# AV_Channel.net
KiCad netlist of a schematic drawn in Altium Designer
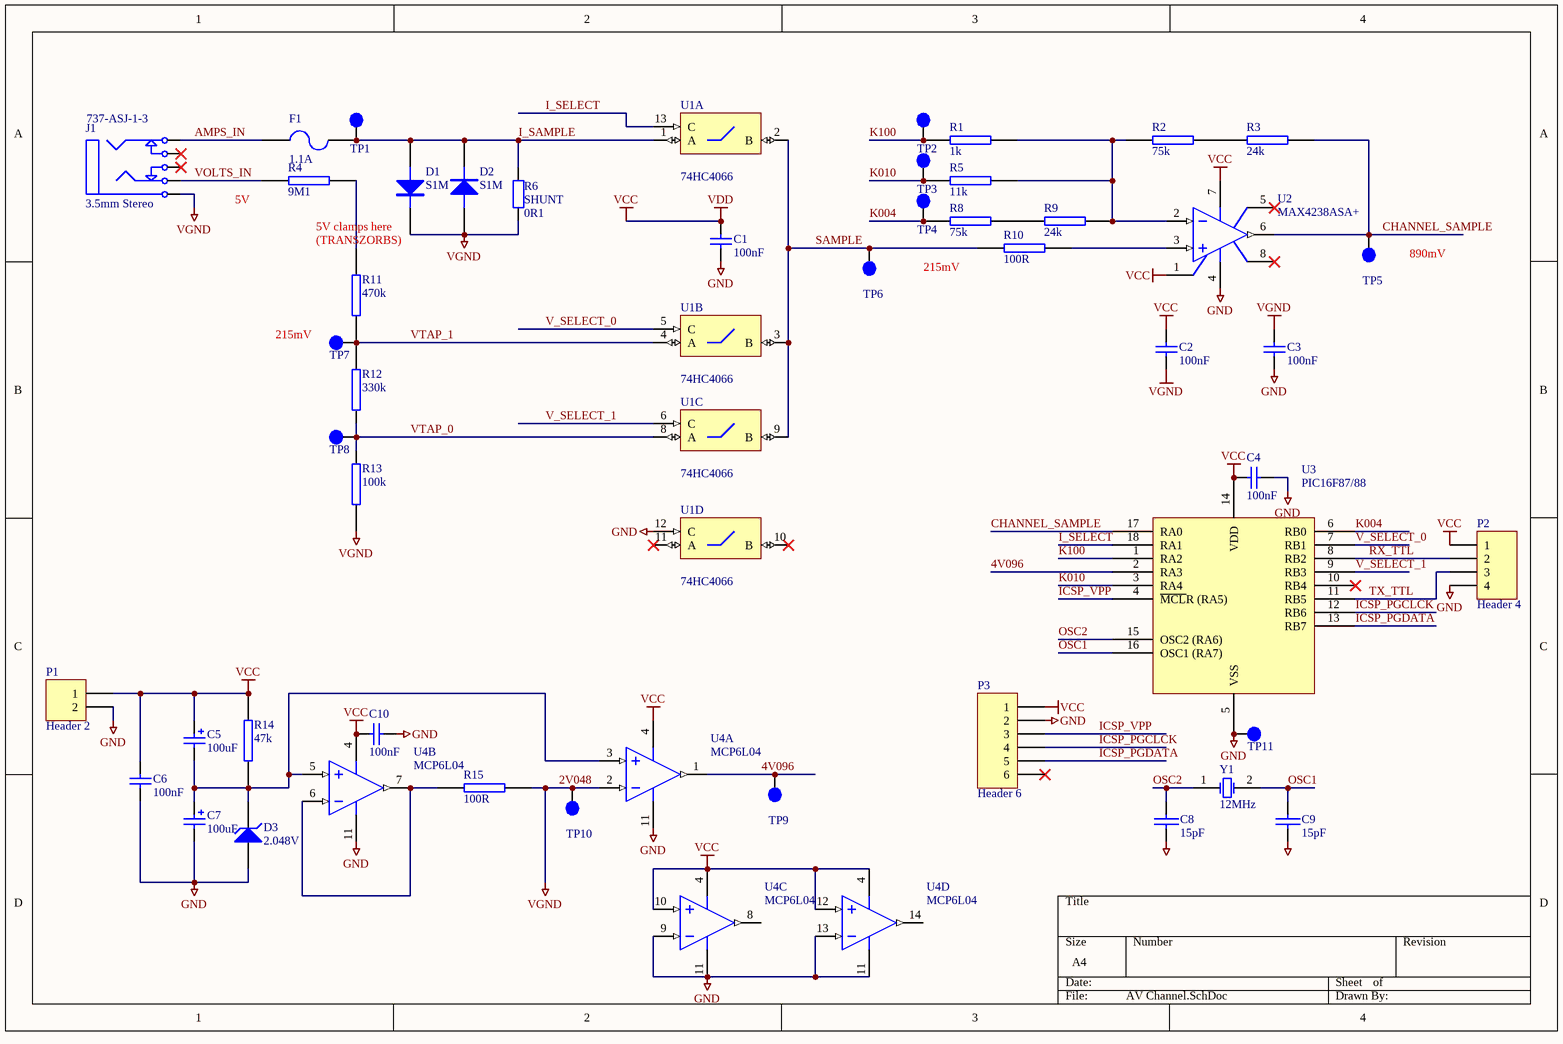
[diagram p0: AV Channel.SchDoc]

(export (version "E")
  (design (tool "Eeschema 10.0.6"))
  (components
    (comp (ref "C1")
      (value "100nF")
      (footprint "CAP (3D) - 0805")
      (description "Capacitor")
      (libsource (lib "Miscellaneous Devices") (part "Cap"))
    )
    (comp (ref "C2")
      (value "100nF")
      (footprint "CAP (3D) - 0805")
      (description "Capacitor")
      (libsource (lib "Miscellaneous Devices") (part "Cap"))
    )
    (comp (ref "C3")
      (value "100nF")
      (footprint "CAP (3D) - 0805")
      (description "Capacitor")
      (libsource (lib "Miscellaneous Devices") (part "Cap"))
    )
    (comp (ref "C4")
      (value "100nF")
      (footprint "CAP (3D) - 0805")
      (description "Capacitor")
      (libsource (lib "Miscellaneous Devices") (part "Cap"))
    )
    (comp (ref "C5")
      (value "100uF")
      (footprint "RB5-10.5")
      (description "CAPACITOR POLARISED TAG B CASE")
      (fields
        (field (name "MANUFACTURER") "Generic Components")
        (field (name "MOUSER PART NO.") "74-293D106X9020B8T")
      )
      (libsource (lib "Mi-Call Schematic") (part "Cap Pol"))
    )
    (comp (ref "C6")
      (value "100nF")
      (footprint "CAP (3D) - 0805")
      (description "Capacitor")
      (libsource (lib "Miscellaneous Devices") (part "Cap"))
    )
    (comp (ref "C7")
      (value "100uF")
      (footprint "RB5-10.5")
      (description "CAPACITOR POLARISED TAG B CASE")
      (fields
        (field (name "MANUFACTURER") "Generic Components")
        (field (name "MOUSER PART NO.") "74-293D106X9020B8T")
      )
      (libsource (lib "Mi-Call Schematic") (part "Cap Pol"))
    )
    (comp (ref "C8")
      (value "15pF")
      (footprint "CAP (3D) - 0805")
      (description "CAPACITOR SMD 0402")
      (fields (field (name "MOUSER PART NO.") "140-CC504N150J-RC") (field (name "MANUFACTURER") "Xicon"))
      (libsource (lib "401 CCPA") (part "CAP"))
    )
    (comp (ref "C9")
      (value "15pF")
      (footprint "CAP (3D) - 0805")
      (description "CAPACITOR SMD 0402")
      (fields (field (name "MOUSER PART NO.") "140-CC504N150J-RC") (field (name "MANUFACTURER") "Xicon"))
      (libsource (lib "401 CCPA") (part "CAP"))
    )
    (comp (ref "C10")
      (value "100nF")
      (footprint "CAP (3D) - 0805")
      (description "Capacitor")
      (libsource (lib "Miscellaneous Devices") (part "Cap"))
    )
    (comp (ref "D1")
      (value "S1M")
      (footprint "DO-214AC")
      (description "DIODE, POWER")
      (fields (field (name "MOUSER PART NO.") "821-S1M") (field (name "MANUFACTURER") "TAIWAN SEMI"))
      (libsource (lib "*") (part "DIODE"))
    )
    (comp (ref "D2")
      (value "S1M")
      (footprint "DO-214AC")
      (description "DIODE, POWER")
      (fields (field (name "MOUSER PART NO.") "821-S1M") (field (name "MANUFACTURER") "TAIWAN SEMI"))
      (libsource (lib "*") (part "DIODE"))
    )
    (comp (ref "D3")
      (value "2.048V")
      (footprint "SOT23-3L")
      (description "LM4040 2.048V Reference")
      (fields (field (name "MOUSER PART NO.") "595-LM4040D20IDBZRG4"))
      (libsource (lib "AV Channel") (part "D Zener"))
    )
    (comp (ref "F1")
      (value "1.1A")
      (footprint "LITTELFUSE 1210")
      (description "Fuse")
      (fields (field (name "MANUFACTURER") "Littlefuse") (field (name "MOUSER PART NO.") "576-1206L110THYR"))
      (libsource (lib "Miscellaneous Devices") (part "Fuse 2"))
    )
    (comp (ref "J1")
      (value "3.5mm Stereo")
      (footprint "3.5MM pcb mouNt")
      (description "3-Conductor Jack with 2 break contacts (normals) and 2 auxiliary make contacts")
      (fields
        (field (name "MOUSER PART NO.") "550-20301")
        (field (name "ALTRONICS PART NO.") "P0073")
        (field (name "SUPPLIER PART NUMBER 1") "737-ASJ-1-3")
      )
      (libsource (lib "NASCO") (part "Phonejack Stereo SW"))
    )
    (comp (ref "P1")
      (value "Header 2")
      (footprint "HDR1X2")
      (description "Header, 2-Pin")
      (fields (field (name "PUBLISHER") "Altium Limited"))
      (libsource (lib "Miscellaneous Connectors") (part "Header 2"))
    )
    (comp (ref "P2")
      (value "Header 4")
      (footprint "HDR1X4")
      (description "Header, 4-Pin")
      (fields (field (name "PUBLISHER") "Altium Limited"))
      (libsource (lib "Miscellaneous Connectors") (part "Header 4"))
    )
    (comp (ref "P3")
      (value "Header 6")
      (footprint "HDR1X6")
      (description "Header, 6-Pin")
      (fields (field (name "PUBLISHER") "Altium Limited"))
      (libsource (lib "Miscellaneous Connectors") (part "Header 6"))
    )
    (comp (ref "R1")
      (value "1k")
      (footprint "RES (3D) - 0805")
      (description "RESISTOR SMD 0603")
      (libsource (lib "NASCO") (part "RES SMD 0603"))
    )
    (comp (ref "R2")
      (value "75k")
      (footprint "RES (3D) - 0805")
      (description "RESISTOR SMD 0603")
      (libsource (lib "NASCO") (part "RES SMD 0603"))
    )
    (comp (ref "R3")
      (value "24k")
      (footprint "RES (3D) - 0805")
      (description "RESISTOR SMD 0603")
      (libsource (lib "NASCO") (part "RES SMD 0603"))
    )
    (comp (ref "R4")
      (value "9M1")
      (footprint "RES (3D) - 0805")
      (description "RESISTOR SMD 0603 10k")
      (fields
        (field (name "MOUSER PART NO.") "71-CRCW0603-8.06M-E3")
        (field (name "MANUFACTURER") "Vishay/Dale")
      )
      (libsource (lib "NASCO Resistors") (part "RES SMD 0603 10k"))
    )
    (comp (ref "R5")
      (value "11k")
      (footprint "RES (3D) - 0805")
      (description "RESISTOR SMD 0603")
      (libsource (lib "NASCO") (part "RES SMD 0603"))
    )
    (comp (ref "R6")
      (value "SHUNT")
      (footprint "5W WW")
      (description "Resistor")
      (fields (field (name "ALTIUM_VALUE") "0R1") (field (name "PUBLISHER") "Altium Limited"))
      (libsource (lib "Miscellaneous Devices") (part "Res2"))
    )
    (comp (ref "R8")
      (value "75k")
      (footprint "RES (3D) - 0805")
      (description "RESISTOR SMD 0603")
      (libsource (lib "NASCO") (part "RES SMD 0603"))
    )
    (comp (ref "R9")
      (value "24k")
      (footprint "RES (3D) - 0805")
      (description "RESISTOR SMD 0603")
      (libsource (lib "NASCO") (part "RES SMD 0603"))
    )
    (comp (ref "R10")
      (value "100R")
      (footprint "RES (3D) - 0805")
      (description "RESISTOR SMD 0603")
      (libsource (lib "NASCO") (part "RES SMD 0603"))
    )
    (comp (ref "R11")
      (value "470k")
      (footprint "RES (3D) - 0805")
      (description "RESISTOR SMD 0603 10k")
      (fields
        (field (name "MOUSER PART NO.") "Vishay/Dale")
        (field (name "MANUFACTURER") "71-CRCW0603-1.62M-E3")
      )
      (libsource (lib "NASCO Resistors") (part "RES SMD 0603 10k"))
    )
    (comp (ref "R12")
      (value "330k")
      (footprint "RES (3D) - 0805")
      (description "RESISTOR SMD 0603 10k")
      (fields
        (field (name "MOUSER PART NO.") "Vishay/Dale")
        (field (name "MANUFACTURER") "71-CRCW0603-1.62M-E3")
      )
      (libsource (lib "NASCO Resistors") (part "RES SMD 0603 10k"))
    )
    (comp (ref "R13")
      (value "100k")
      (footprint "RES (3D) - 0805")
      (description "RESISTOR SMD 0603 10k")
      (fields
        (field (name "MOUSER PART NO.") "Vishay/Dale")
        (field (name "MANUFACTURER") "71-CRCW0603-1.62M-E3")
      )
      (libsource (lib "NASCO Resistors") (part "RES SMD 0603 10k"))
    )
    (comp (ref "R14")
      (value "47k")
      (footprint "RES (3D) - 0805")
      (description "RESISTOR SMD 0603 10k")
      (fields (field (name "MOUSER PART NO.") "652-CR0603FX-1002ELF") (field (name "MANUFACTURER") "Bourns"))
      (libsource (lib "NASCO Resistors") (part "RES SMD 0603 10k"))
    )
    (comp (ref "R15")
      (value "100R")
      (footprint "RES (3D) - 0805")
      (description "RESISTOR SMD 0603")
      (libsource (lib "NASCO") (part "RES SMD 0603"))
    )
    (comp (ref "TP1") (value "TestPoint") (footprint "TP") (libsource (lib "NASCO") (part "TestPoint")))
    (comp (ref "TP2") (value "TestPoint") (footprint "TP") (libsource (lib "NASCO") (part "TestPoint")))
    (comp (ref "TP3") (value "TestPoint") (footprint "TP") (libsource (lib "NASCO") (part "TestPoint")))
    (comp (ref "TP4") (value "TestPoint") (footprint "TP") (libsource (lib "NASCO") (part "TestPoint")))
    (comp (ref "TP5") (value "TestPoint") (footprint "TP") (libsource (lib "NASCO") (part "TestPoint")))
    (comp (ref "TP6") (value "TestPoint") (footprint "TP") (libsource (lib "NASCO") (part "TestPoint")))
    (comp (ref "TP7") (value "TestPoint") (footprint "TP") (libsource (lib "NASCO") (part "TestPoint")))
    (comp (ref "TP8") (value "TestPoint") (footprint "TP") (libsource (lib "NASCO") (part "TestPoint")))
    (comp (ref "TP9") (value "TestPoint") (footprint "TP") (libsource (lib "NASCO") (part "TestPoint")))
    (comp (ref "TP10") (value "TestPoint") (footprint "TP") (libsource (lib "NASCO") (part "TestPoint")))
    (comp (ref "TP11") (value "TestPoint") (footprint "TP") (libsource (lib "NASCO") (part "TestPoint")))
    (comp (ref "U1")
      (value "74HC4066")
      (footprint "DIP-14")
      (description "Quadruple Bilateral Analog Switch")
      (libsource (lib "NASCO") (part "74HC4066"))
    )
    (comp (ref "U2")
      (value "MAX4238ASA+")
      (footprint "SO-8")
      (description "Single Voltage-Feedback Operational Amplifier")
      (fields (field (name "PUBLISHER") "Altium Limited"))
      (libsource (lib "Maxim Operational Amplifier") (part "MAX495CSA"))
    )
    (comp (ref "U3")
      (value "PIC16F87/88")
      (footprint "SOIC-18")
      (description "PIC16F88")
      (fields
        (field (name "MOUSER PART NO.") "579-PIC16F88-E/SS")
        (field (name "FARNELL PART NO.") "9761519")
      )
      (libsource (lib "NASCO") (part "PIC16F87/88"))
    )
    (comp (ref "U4")
      (value "MCP6L04")
      (footprint "SO-14")
      (libsource (lib "Microchip Opamps") (part "MCP6L04"))
    )
    (comp (ref "Y1")
      (value "12MHz")
      (footprint "HC49/4H_SMX")
      (description "Crystal Oscillator")
      (fields (field (name "MANUFACTURER") "ECS") (field (name "MANUFACTURER PART NO.") "ECS-160-20-5PX-TR"))
      (libsource (lib "Miscellaneous Devices") (part "XTAL"))
    )
  )
  (nets
    (net (code "1") (name "/4V096") (class "Default")
      (node (ref "TP9") (pin "1") (pinfunction "1_1") (pintype "passive"))
      (node (ref "U3") (pin "2") (pinfunction "RA3_2") (pintype "passive"))
      (node (ref "U4") (pin "1") (pinfunction "OUTA_1") (pintype "output"))
    )
    (net (code "2") (name "/AMPS_IN") (class "Default")
      (node (ref "F1") (pin "1") (pinfunction "1_1") (pintype "passive"))
      (node (ref "J1") (pin "5") (pinfunction "5_5") (pintype "passive"))
    )
    (net (code "3") (name "/CHANNEL_SAMPLE") (class "Default")
      (node (ref "R3") (pin "2") (pinfunction "2_2") (pintype "passive"))
      (node (ref "TP5") (pin "1") (pinfunction "1_1") (pintype "passive"))
      (node (ref "U2") (pin "6") (pinfunction "OUT_6") (pintype "output"))
      (node (ref "U3") (pin "17") (pinfunction "RA0_17") (pintype "passive"))
    )
    (net (code "4") (name "/ICSP_PGCLCK") (class "Default")
      (node (ref "P3") (pin "4") (pinfunction "4_4") (pintype "passive"))
      (node (ref "U3") (pin "12") (pinfunction "RB6_12") (pintype "passive"))
    )
    (net (code "5") (name "/ICSP_PGDATA") (class "Default")
      (node (ref "P3") (pin "5") (pinfunction "5_5") (pintype "passive"))
      (node (ref "U3") (pin "13") (pinfunction "RB7_13") (pintype "passive"))
    )
    (net (code "6") (name "/ICSP_VPP") (class "Default")
      (node (ref "P3") (pin "3") (pinfunction "3_3") (pintype "passive"))
      (node (ref "U3") (pin "4") (pinfunction "~{MCL}R_(RA5)_4") (pintype "passive"))
    )
    (net (code "7") (name "/I_SAMPLE") (class "Default")
      (node (ref "D1") (pin "1") (pinfunction "A_1") (pintype "passive"))
      (node (ref "D2") (pin "2") (pinfunction "K_2") (pintype "passive"))
      (node (ref "F1") (pin "2") (pinfunction "2_2") (pintype "passive"))
      (node (ref "R6") (pin "2") (pinfunction "2_2") (pintype "passive"))
      (node (ref "TP1") (pin "1") (pinfunction "1_1") (pintype "passive"))
      (node (ref "U1") (pin "1") (pinfunction "A_1") (pintype "bidirectional"))
    )
    (net (code "8") (name "/I_SELECT") (class "Default")
      (node (ref "U1") (pin "13") (pinfunction "C_13") (pintype "input"))
      (node (ref "U3") (pin "18") (pinfunction "RA1_18") (pintype "passive"))
    )
    (net (code "9") (name "/K004") (class "Default")
      (node (ref "R8") (pin "1") (pinfunction "1_1") (pintype "passive"))
      (node (ref "TP4") (pin "1") (pinfunction "1_1") (pintype "passive"))
      (node (ref "U3") (pin "6") (pinfunction "RB0_6") (pintype "passive"))
    )
    (net (code "10") (name "/K010") (class "Default")
      (node (ref "R5") (pin "1") (pinfunction "1_1") (pintype "passive"))
      (node (ref "TP3") (pin "1") (pinfunction "1_1") (pintype "passive"))
      (node (ref "U3") (pin "3") (pinfunction "RA4_3") (pintype "passive"))
    )
    (net (code "11") (name "/K100") (class "Default")
      (node (ref "R1") (pin "1") (pinfunction "1_1") (pintype "passive"))
      (node (ref "TP2") (pin "1") (pinfunction "1_1") (pintype "passive"))
      (node (ref "U3") (pin "1") (pinfunction "RA2_1") (pintype "passive"))
    )
    (net (code "12") (name "/OSC1") (class "Default")
      (node (ref "C9") (pin "1") (pinfunction "1_1") (pintype "passive"))
      (node (ref "U3") (pin "16") (pinfunction "OSC1_(RA7)_16") (pintype "passive"))
      (node (ref "Y1") (pin "2") (pinfunction "OSC2_2") (pintype "passive"))
    )
    (net (code "13") (name "/OSC2") (class "Default")
      (node (ref "C8") (pin "1") (pinfunction "1_1") (pintype "passive"))
      (node (ref "U3") (pin "15") (pinfunction "OSC2_(RA6)_15") (pintype "passive"))
      (node (ref "Y1") (pin "1") (pinfunction "OSC1_1") (pintype "passive"))
    )
    (net (code "14") (name "/RX_TTL") (class "Default")
      (node (ref "P2") (pin "2") (pinfunction "2_2") (pintype "passive"))
      (node (ref "U3") (pin "8") (pinfunction "RB2_8") (pintype "passive"))
    )
    (net (code "15") (name "/SAMPLE") (class "Default")
      (node (ref "R10") (pin "1") (pinfunction "1_1") (pintype "passive"))
      (node (ref "TP6") (pin "1") (pinfunction "1_1") (pintype "passive"))
      (node (ref "U1") (pin "2") (pinfunction "B_2") (pintype "bidirectional"))
      (node (ref "U1") (pin "3") (pinfunction "B_3") (pintype "bidirectional"))
      (node (ref "U1") (pin "9") (pinfunction "B_9") (pintype "bidirectional"))
    )
    (net (code "16") (name "/TX_TTL") (class "Default")
      (node (ref "P2") (pin "3") (pinfunction "3_3") (pintype "passive"))
      (node (ref "U3") (pin "11") (pinfunction "RB5_11") (pintype "passive"))
    )
    (net (code "17") (name "/VOLTS_IN") (class "Default")
      (node (ref "J1") (pin "2") (pinfunction "2_2") (pintype "passive"))
      (node (ref "R4") (pin "1") (pinfunction "1_1") (pintype "passive"))
    )
    (net (code "18") (name "/VTAP_0") (class "Default")
      (node (ref "R12") (pin "2") (pinfunction "2_2") (pintype "passive"))
      (node (ref "R13") (pin "1") (pinfunction "1_1") (pintype "passive"))
      (node (ref "TP8") (pin "1") (pinfunction "1_1") (pintype "passive"))
      (node (ref "U1") (pin "8") (pinfunction "A_8") (pintype "bidirectional"))
    )
    (net (code "19") (name "/VTAP_1") (class "Default")
      (node (ref "R11") (pin "2") (pinfunction "2_2") (pintype "passive"))
      (node (ref "R12") (pin "1") (pinfunction "1_1") (pintype "passive"))
      (node (ref "TP7") (pin "1") (pinfunction "1_1") (pintype "passive"))
      (node (ref "U1") (pin "4") (pinfunction "A_4") (pintype "bidirectional"))
    )
    (net (code "20") (name "/V_SELECT_0") (class "Default")
      (node (ref "U1") (pin "5") (pinfunction "C_5") (pintype "input"))
      (node (ref "U3") (pin "7") (pinfunction "RB1_7") (pintype "passive"))
    )
    (net (code "21") (name "/V_SELECT_1") (class "Default")
      (node (ref "U1") (pin "6") (pinfunction "C_6") (pintype "input"))
      (node (ref "U3") (pin "9") (pinfunction "RB3_9") (pintype "passive"))
    )
    (net (code "22") (name "GND") (class "Default")
      (node (ref "C1") (pin "1") (pinfunction "1_1") (pintype "passive"))
      (node (ref "C10") (pin "2") (pinfunction "2_2") (pintype "passive"))
      (node (ref "C3") (pin "1") (pinfunction "1_1") (pintype "passive"))
      (node (ref "C4") (pin "2") (pinfunction "2_2") (pintype "passive"))
      (node (ref "C6") (pin "1") (pinfunction "1_1") (pintype "passive"))
      (node (ref "C7") (pin "2") (pinfunction "2_2") (pintype "passive"))
      (node (ref "C8") (pin "2") (pinfunction "2_2") (pintype "passive"))
      (node (ref "C9") (pin "2") (pinfunction "2_2") (pintype "passive"))
      (node (ref "D3") (pin "2") (pinfunction "A_2") (pintype "passive"))
      (node (ref "P1") (pin "2") (pinfunction "2_2") (pintype "passive"))
      (node (ref "P2") (pin "4") (pinfunction "4_4") (pintype "passive"))
      (node (ref "P3") (pin "2") (pinfunction "2_2") (pintype "passive"))
      (node (ref "TP11") (pin "1") (pinfunction "1_1") (pintype "passive"))
      (node (ref "U1") (pin "12") (pinfunction "C_12") (pintype "input"))
      (node (ref "U1") (pin "7") (pinfunction "GND_7") (pintype "power_in"))
      (node (ref "U2") (pin "4") (pinfunction "VEE_4") (pintype "power_in"))
      (node (ref "U3") (pin "5") (pinfunction "VSS_5") (pintype "passive"))
      (node (ref "U4") (pin "11") (pinfunction "VSS_11") (pintype "power_in"))
      (node (ref "U4") (pin "13") (pinfunction "INC-_13") (pintype "input"))
      (node (ref "U4") (pin "9") (pinfunction "INC-_9") (pintype "input"))
    )
    (net (code "23") (name "Net-(D3-K)") (class "Default")
      (node (ref "C5") (pin "2") (pinfunction "2_2") (pintype "passive"))
      (node (ref "C7") (pin "1") (pinfunction "1_1") (pintype "passive"))
      (node (ref "D3") (pin "1") (pinfunction "K_1") (pintype "passive"))
      (node (ref "R14") (pin "1") (pinfunction "1_1") (pintype "passive"))
      (node (ref "U4") (pin "3") (pinfunction "INA+_3") (pintype "input"))
      (node (ref "U4") (pin "5") (pinfunction "INB+_5") (pintype "input"))
    )
    (net (code "24") (name "Net-(R2-Pad2)") (class "Default")
      (node (ref "R2") (pin "2") (pinfunction "2_2") (pintype "passive"))
      (node (ref "R3") (pin "1") (pinfunction "1_1") (pintype "passive"))
    )
    (net (code "25") (name "Net-(R8-Pad2)") (class "Default")
      (node (ref "R8") (pin "2") (pinfunction "2_2") (pintype "passive"))
      (node (ref "R9") (pin "1") (pinfunction "1_1") (pintype "passive"))
    )
    (net (code "26") (name "Net-(R11-Pad1)") (class "Default")
      (node (ref "R11") (pin "1") (pinfunction "1_1") (pintype "passive"))
      (node (ref "R4") (pin "2") (pinfunction "2_2") (pintype "passive"))
    )
    (net (code "27") (name "Net-(U2-IN+)") (class "Default")
      (node (ref "R10") (pin "2") (pinfunction "2_2") (pintype "passive"))
      (node (ref "U2") (pin "3") (pinfunction "IN+_3") (pintype "input"))
    )
    (net (code "28") (name "Net-(U2-IN-)") (class "Default")
      (node (ref "R1") (pin "2") (pinfunction "2_2") (pintype "passive"))
      (node (ref "R2") (pin "1") (pinfunction "1_1") (pintype "passive"))
      (node (ref "R5") (pin "2") (pinfunction "2_2") (pintype "passive"))
      (node (ref "R9") (pin "2") (pinfunction "2_2") (pintype "passive"))
      (node (ref "U2") (pin "2") (pinfunction "IN-_2") (pintype "input"))
    )
    (net (code "29") (name "Net-(U4B-INB-)") (class "Default")
      (node (ref "R15") (pin "1") (pinfunction "1_1") (pintype "passive"))
      (node (ref "U4") (pin "6") (pinfunction "INB-_6") (pintype "input"))
      (node (ref "U4") (pin "7") (pinfunction "OUTB_7") (pintype "output"))
    )
    (net (code "30") (name "VCC") (class "Default")
      (node (ref "C1") (pin "2") (pinfunction "2_2") (pintype "passive"))
      (node (ref "C10") (pin "1") (pinfunction "1_1") (pintype "passive"))
      (node (ref "C2") (pin "2") (pinfunction "2_2") (pintype "passive"))
      (node (ref "C4") (pin "1") (pinfunction "1_1") (pintype "passive"))
      (node (ref "C5") (pin "1") (pinfunction "1_1") (pintype "passive"))
      (node (ref "C6") (pin "2") (pinfunction "2_2") (pintype "passive"))
      (node (ref "P1") (pin "1") (pinfunction "1_1") (pintype "passive"))
      (node (ref "P2") (pin "1") (pinfunction "1_1") (pintype "passive"))
      (node (ref "P3") (pin "1") (pinfunction "1_1") (pintype "passive"))
      (node (ref "R14") (pin "2") (pinfunction "2_2") (pintype "passive"))
      (node (ref "U1") (pin "14") (pinfunction "VDD_14") (pintype "power_in"))
      (node (ref "U2") (pin "1") (pinfunction "NULL_1") (pintype "passive"))
      (node (ref "U2") (pin "7") (pinfunction "VCC_7") (pintype "power_in"))
      (node (ref "U3") (pin "14") (pinfunction "VDD_14") (pintype "passive"))
      (node (ref "U4") (pin "10") (pinfunction "INC+_10") (pintype "input"))
      (node (ref "U4") (pin "12") (pinfunction "INC+_12") (pintype "input"))
      (node (ref "U4") (pin "4") (pinfunction "VDD_4") (pintype "power_in"))
    )
    (net (code "31") (name "VGND") (class "Default")
      (node (ref "C2") (pin "1") (pinfunction "1_1") (pintype "passive"))
      (node (ref "C3") (pin "2") (pinfunction "2_2") (pintype "passive"))
      (node (ref "D1") (pin "2") (pinfunction "K_2") (pintype "passive"))
      (node (ref "D2") (pin "1") (pinfunction "A_1") (pintype "passive"))
      (node (ref "J1") (pin "1") (pinfunction "1_1") (pintype "passive"))
      (node (ref "R13") (pin "2") (pinfunction "2_2") (pintype "passive"))
      (node (ref "R15") (pin "2") (pinfunction "2_2") (pintype "passive"))
      (node (ref "R6") (pin "1") (pinfunction "1_1") (pintype "passive"))
      (node (ref "TP10") (pin "1") (pinfunction "1_1") (pintype "passive"))
      (node (ref "U4") (pin "2") (pinfunction "INA-_2") (pintype "input"))
    )
    (net (code "32") (name "unconnected-(J1-Pad3)") (class "Default")
      (node (ref "J1") (pin "3") (pinfunction "3_3") (pintype "passive+no_connect"))
    )
    (net (code "33") (name "unconnected-(J1-Pad4)") (class "Default")
      (node (ref "J1") (pin "4") (pinfunction "4_4") (pintype "passive+no_connect"))
    )
    (net (code "34") (name "unconnected-(P3-Pad6)") (class "Default")
      (node (ref "P3") (pin "6") (pinfunction "6_6") (pintype "passive+no_connect"))
    )
    (net (code "35") (name "unconnected-(U1D-A-Pad11)") (class "Default")
      (node (ref "U1") (pin "11") (pinfunction "A_11") (pintype "bidirectional+no_connect"))
    )
    (net (code "36") (name "unconnected-(U1D-B-Pad10)") (class "Default")
      (node (ref "U1") (pin "10") (pinfunction "B_10") (pintype "bidirectional+no_connect"))
    )
    (net (code "37") (name "unconnected-(U2-NC-Pad8)") (class "Default")
      (node (ref "U2") (pin "8") (pinfunction "NC_8") (pintype "passive+no_connect"))
    )
    (net (code "38") (name "unconnected-(U2-NULL-Pad5)") (class "Default")
      (node (ref "U2") (pin "5") (pinfunction "NULL_5") (pintype "passive+no_connect"))
    )
    (net (code "39") (name "unconnected-(U3-RB4-Pad10)") (class "Default")
      (node (ref "U3") (pin "10") (pinfunction "RB4_10") (pintype "passive+no_connect"))
    )
    (net (code "40") (name "unconnected-(U4C-OUTC-Pad8)") (class "Default")
      (node (ref "U4") (pin "8") (pinfunction "OUTC_8") (pintype "output"))
    )
    (net (code "41") (name "unconnected-(U4D-OUTD-Pad14)") (class "Default")
      (node (ref "U4") (pin "14") (pinfunction "OUTD_14") (pintype "output"))
    )
  )
)
